# VoltageDivider.net
KiCad netlist of a schematic drawn in EAGLE
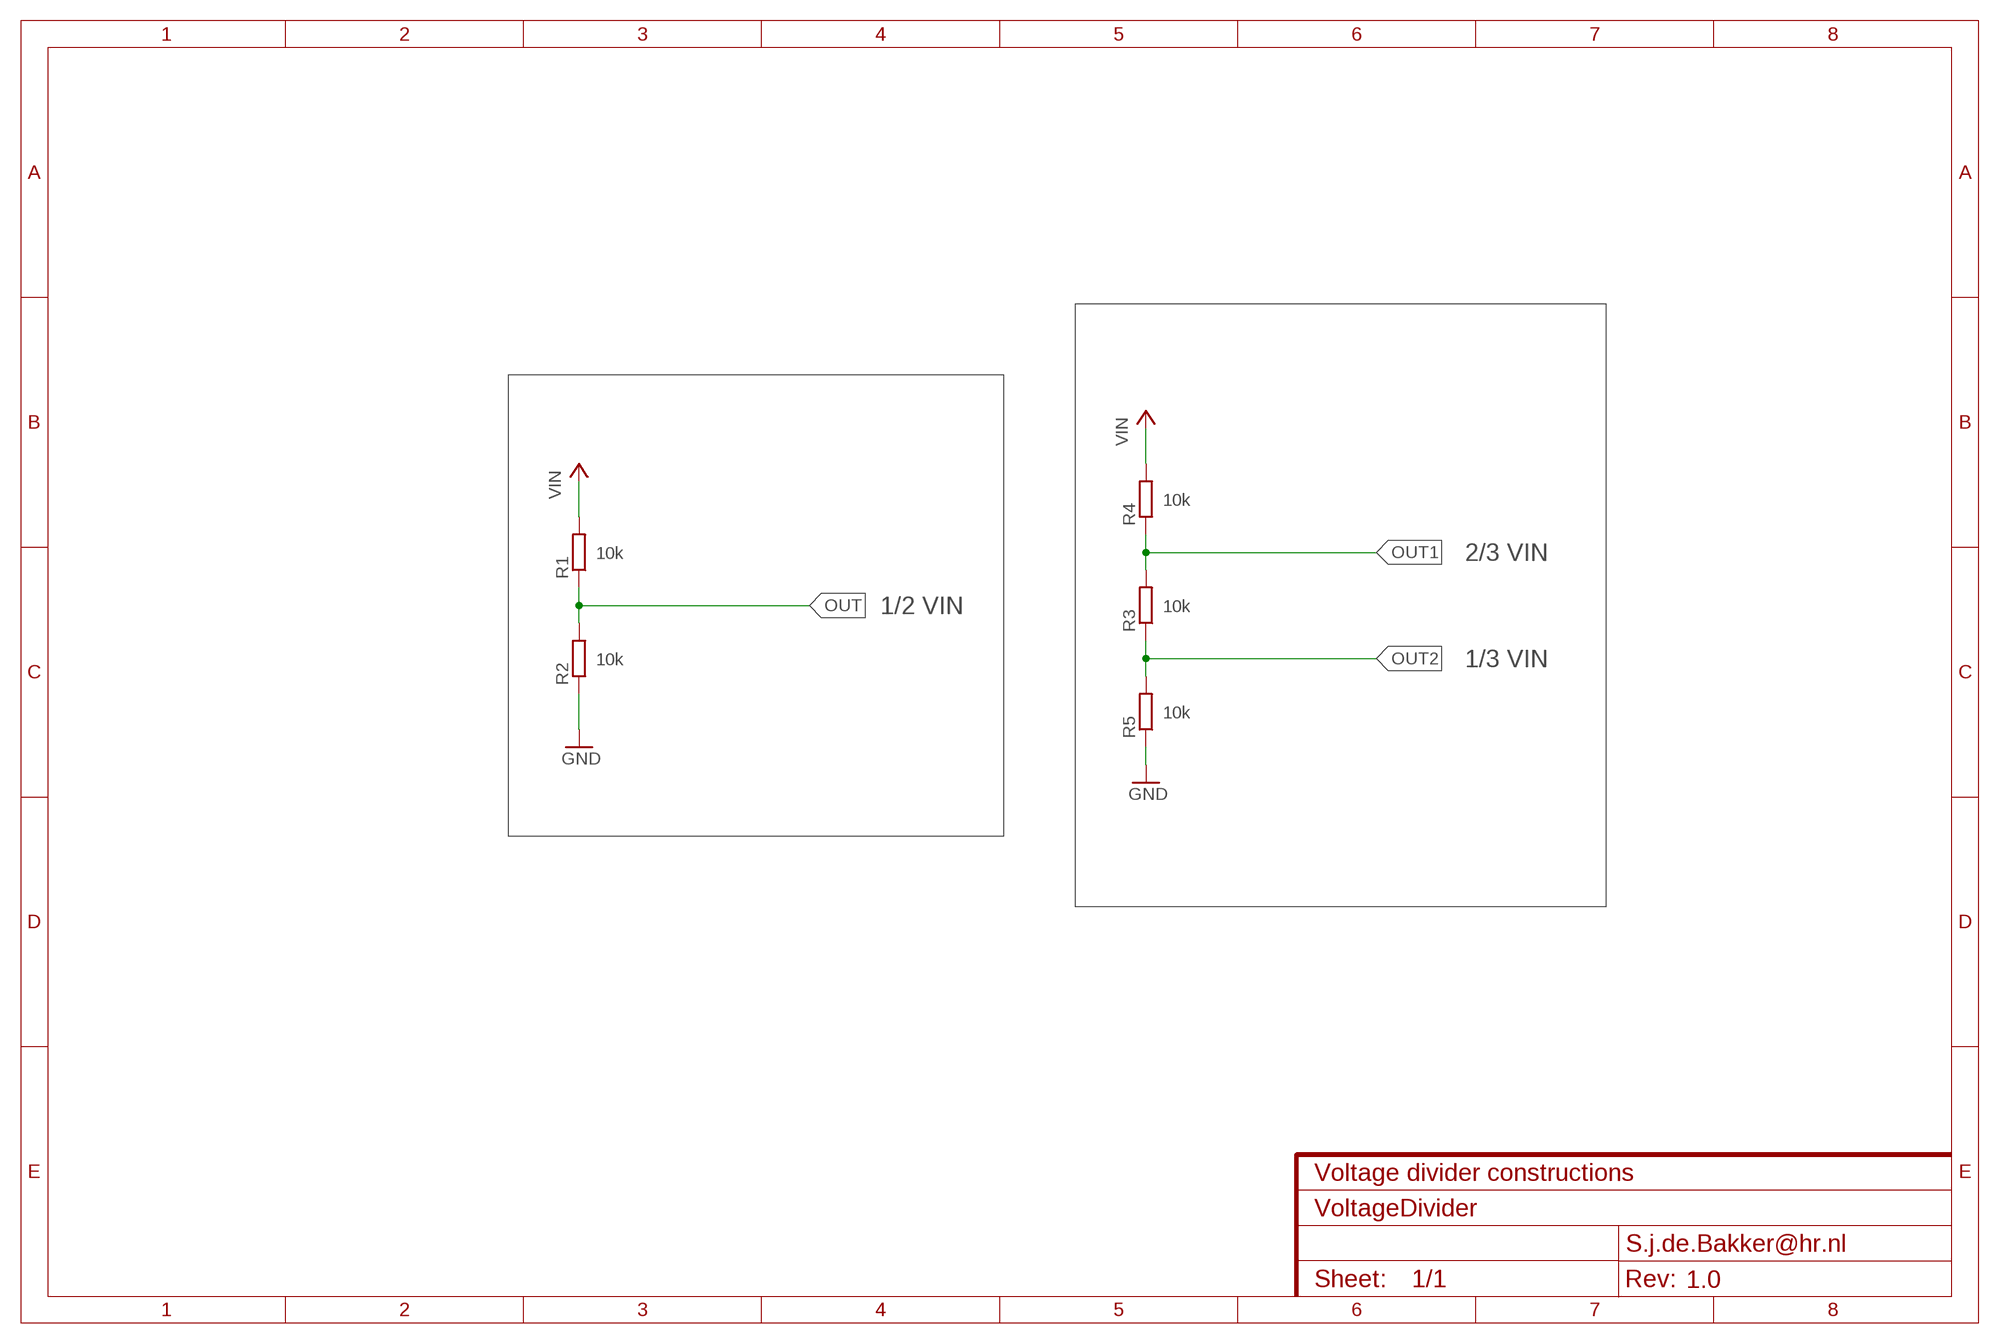
[diagram p0: schematic, sheet 1]

(export (version "E")
  (design (tool "Eeschema 10.0.6"))
  (components
    (comp (ref "R1")
      (value "10k")
      (footprint "eagle-import:VTA52")
      (libsource (lib "eagle-import") (part "R-EU_VTA52"))
    )
    (comp (ref "R2")
      (value "10k")
      (footprint "eagle-import:VTA52")
      (libsource (lib "eagle-import") (part "R-EU_VTA52"))
    )
    (comp (ref "R3")
      (value "10k")
      (footprint "eagle-import:VTA52")
      (libsource (lib "eagle-import") (part "R-EU_VTA52"))
    )
    (comp (ref "R4")
      (value "10k")
      (footprint "eagle-import:VTA52")
      (libsource (lib "eagle-import") (part "R-EU_VTA52"))
    )
    (comp (ref "R5")
      (value "10k")
      (footprint "eagle-import:VTA52")
      (libsource (lib "eagle-import") (part "R-EU_VTA52"))
    )
  )
  (nets
    (net (code "1") (name "GND") (class "Default")
      (node (ref "R2") (pin "1") (pinfunction "1_1") (pintype "passive"))
      (node (ref "R5") (pin "1") (pinfunction "1_1") (pintype "passive"))
    )
    (net (code "2") (name "OUT") (class "Default")
      (node (ref "R1") (pin "1") (pinfunction "1_1") (pintype "passive"))
      (node (ref "R2") (pin "2") (pinfunction "2_2") (pintype "passive"))
    )
    (net (code "3") (name "OUT1") (class "Default")
      (node (ref "R3") (pin "2") (pinfunction "2_2") (pintype "passive"))
      (node (ref "R4") (pin "1") (pinfunction "1_1") (pintype "passive"))
    )
    (net (code "4") (name "OUT2") (class "Default")
      (node (ref "R3") (pin "1") (pinfunction "1_1") (pintype "passive"))
      (node (ref "R5") (pin "2") (pinfunction "2_2") (pintype "passive"))
    )
    (net (code "5") (name "VIN") (class "Default")
      (node (ref "R1") (pin "2") (pinfunction "2_2") (pintype "passive"))
      (node (ref "R4") (pin "2") (pinfunction "2_2") (pintype "passive"))
    )
  )
)
